# Power.net
KiCad netlist of a schematic drawn in Altium Designer
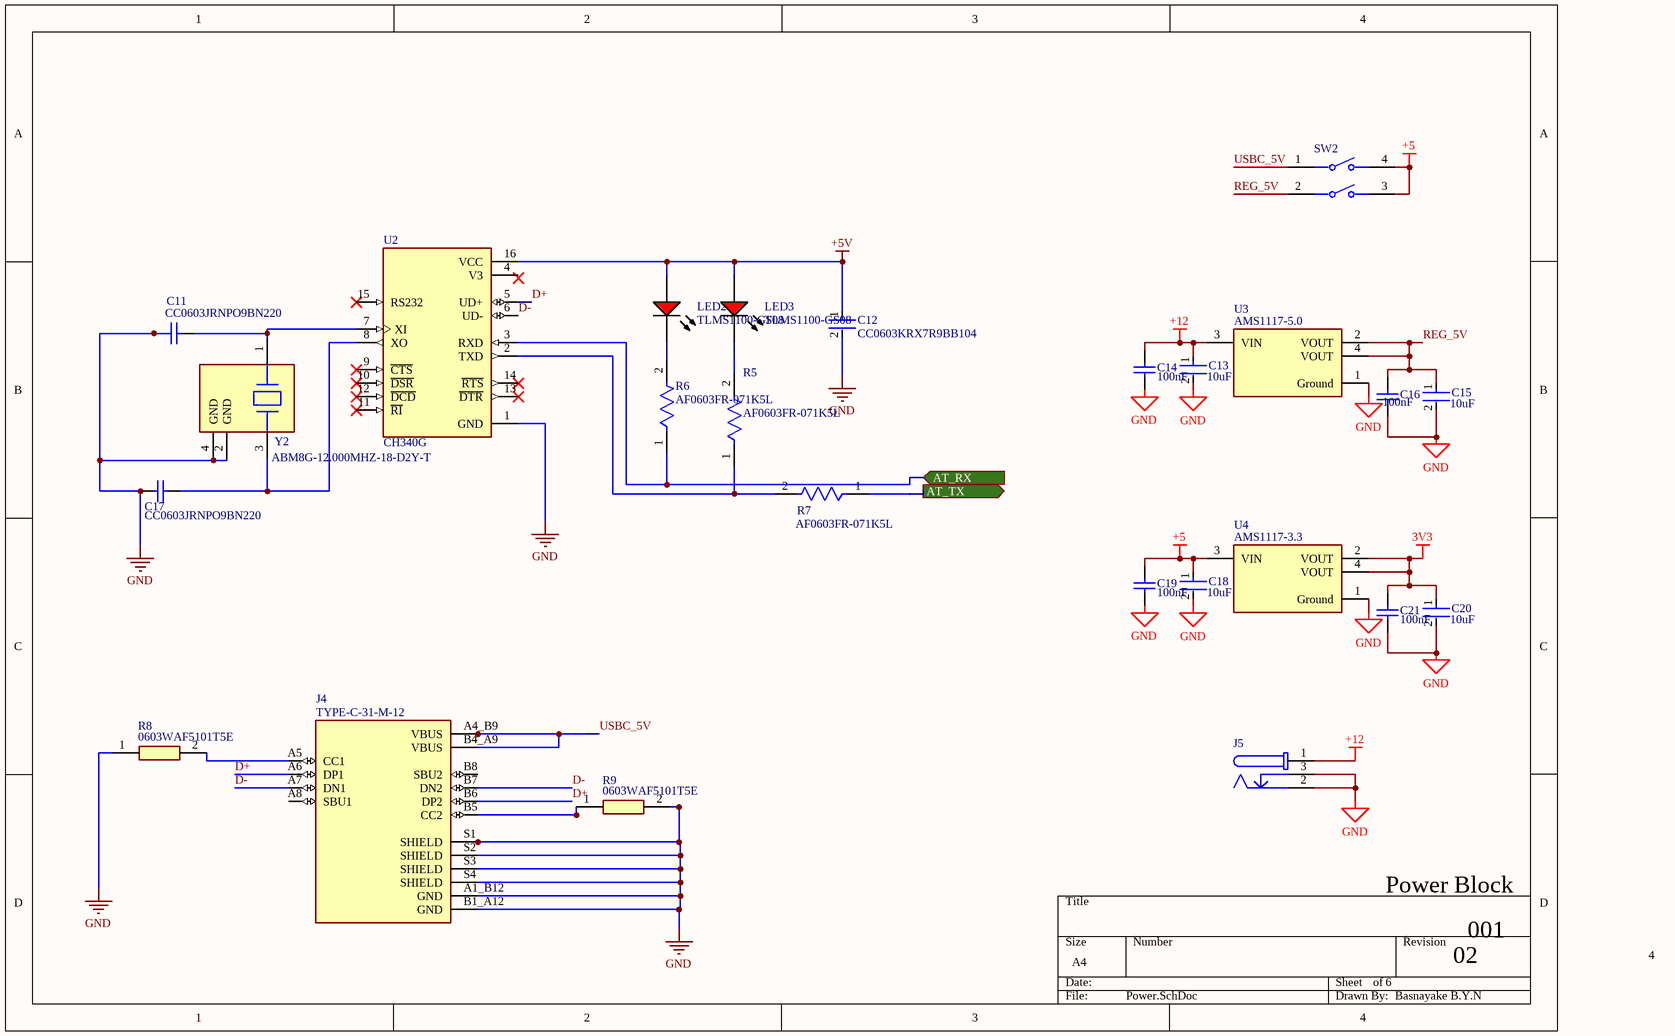
[diagram p0: Power.SchDoc]

(export (version "E")
  (design (tool "Eeschema 10.0.6"))
  (components
    (comp (ref "C11")
      (value "CC0603JRNPO9BN220")
      (footprint "CAPC1608X90X40LL10T20")
      (description "Chip Capacitor, 22 pF, +/- 5%, 50 V, -55 to 125 degC, 0603 (1608 Metric), RoHS, Tape and Reel")
      (libsource (lib "Altium Content Vault") (part "CAP-NP-2"))
    )
    (comp (ref "C12")
      (value "CC0603KRX7R9BB104")
      (footprint "FP-CC0603-DA-MFG")
      (description "CAP CER 0.1UF 50V X7R 0603")
      (fields (field (name "MANUFACTURER") "YAGEO") (field (name "VOLTAGE") "50 V"))
      (libsource (lib "Altium Content Vault") (part "11868f565c42a9108669ba33697ecf6"))
    )
    (comp (ref "C13")
      (value "1206YD106KAT2A")
      (footprint "FP-1206-L_3_2_0_2-W_1_6_0-IPC_B")
      (description "General Purpose Ceramic Capacitor, 1206, 10uF, 10%, X5R, 15%, 16V")
      (fields
        (field (name "TOLERANCE") "10%")
        (field (name "CAPACITANCE") "10uF")
        (field (name "VOLTAGE") "16V")
      )
      (libsource (lib "Altium Content Vault") (part "02cd4be3c70576c341d710602a673aa"))
    )
    (comp (ref "C14")
      (value "100nF")
      (footprint "CAPC2013X140X50LL20T25")
      (fields
        (field (name "MANUFACTURER") "AVX Interconnect / Elco")
        (field (name "PART NUMBER") "08055F104KAT2A")
      )
      (libsource (lib "Altium Content Vault") (part "CAP"))
    )
    (comp (ref "C15")
      (value "1206YD106KAT2A")
      (footprint "FP-1206-L_3_2_0_2-W_1_6_0-IPC_B")
      (description "General Purpose Ceramic Capacitor, 1206, 10uF, 10%, X5R, 15%, 16V")
      (fields
        (field (name "TOLERANCE") "10%")
        (field (name "CAPACITANCE") "10uF")
        (field (name "VOLTAGE") "16V")
      )
      (libsource (lib "Altium Content Vault") (part "02cd4be3c70576c341d710602a673aa"))
    )
    (comp (ref "C16")
      (value "100nF")
      (footprint "CAPC2013X140X50LL20T25")
      (fields
        (field (name "MANUFACTURER") "AVX Interconnect / Elco")
        (field (name "PART NUMBER") "08055F104KAT2A")
      )
      (libsource (lib "Altium Content Vault") (part "CAP"))
    )
    (comp (ref "C17")
      (value "CC0603JRNPO9BN220")
      (footprint "CAPC1608X90X40LL10T20")
      (description "Chip Capacitor, 22 pF, +/- 5%, 50 V, -55 to 125 degC, 0603 (1608 Metric), RoHS, Tape and Reel")
      (libsource (lib "Altium Content Vault") (part "CAP-NP-2"))
    )
    (comp (ref "C18")
      (value "1206YD106KAT2A")
      (footprint "FP-1206-L_3_2_0_2-W_1_6_0-IPC_B")
      (description "General Purpose Ceramic Capacitor, 1206, 10uF, 10%, X5R, 15%, 16V")
      (fields
        (field (name "TOLERANCE") "10%")
        (field (name "CAPACITANCE") "10uF")
        (field (name "VOLTAGE") "16V")
      )
      (libsource (lib "Altium Content Vault") (part "02cd4be3c70576c341d710602a673aa"))
    )
    (comp (ref "C19")
      (value "100nF")
      (footprint "CAPC2013X140X50LL20T25")
      (fields
        (field (name "MANUFACTURER") "AVX Interconnect / Elco")
        (field (name "PART NUMBER") "08055F104KAT2A")
      )
      (libsource (lib "Altium Content Vault") (part "CAP"))
    )
    (comp (ref "C20")
      (value "1206YD106KAT2A")
      (footprint "FP-1206-L_3_2_0_2-W_1_6_0-IPC_B")
      (description "General Purpose Ceramic Capacitor, 1206, 10uF, 10%, X5R, 15%, 16V")
      (fields
        (field (name "TOLERANCE") "10%")
        (field (name "CAPACITANCE") "10uF")
        (field (name "VOLTAGE") "16V")
      )
      (libsource (lib "Altium Content Vault") (part "02cd4be3c70576c341d710602a673aa"))
    )
    (comp (ref "C21")
      (value "100nF")
      (footprint "CAPC2013X140X50LL20T25")
      (fields
        (field (name "MANUFACTURER") "AVX Interconnect / Elco")
        (field (name "PART NUMBER") "08055F104KAT2A")
      )
      (libsource (lib "Altium Content Vault") (part "CAP"))
    )
    (comp (ref "J4")
      (value "TYPE-C-31-M-12")
      (footprint "HRO_TYPE-C-31-M-12")
      (description "USB Connectors 24 Receptacle 1 8.94*7.3mm RoHS")
      (fields (field (name "MF") "HRO Electronics Co., Ltd."))
      (libsource (lib "EarendelPro_Track") (part "TYPE-C-31-M-12"))
    )
    (comp (ref "J5")
      (value "694106301002")
      (footprint "694106301002")
      (libsource (lib "Altium Content Vault") (part "DC Power Jack"))
    )
    (comp (ref "LED2")
      (value "TLMS1100-GS08")
      (footprint "VISH-TLMX1100_V")
      (description "LED, RED, 2.1 V, -40 to 100 degC, 2-Pin SMD (0603), RoHS, Tape and Reel")
      (fields (field (name "TOLERANCE") "5%"))
      (libsource (lib "Altium Content Vault") (part "LED-RED-AK-2"))
    )
    (comp (ref "LED3")
      (value "TLMS1100-GS08")
      (footprint "VISH-TLMX1100_V")
      (description "LED, RED, 2.1 V, -40 to 100 degC, 2-Pin SMD (0603), RoHS, Tape and Reel")
      (fields (field (name "TOLERANCE") "5%"))
      (libsource (lib "Altium Content Vault") (part "LED-RED-AK-2"))
    )
    (comp (ref "R5")
      (value "AF0603FR-071K5L")
      (footprint "FP-AF0603-IPC_B")
      (description "Anti-Sulfurated Chip Resistors Automotive Grade 1.5kΩ 1% 100ppm/°C 0603")
      (fields (field (name "TOLERANCE") "1%"))
      (libsource (lib "Altium Content Vault") (part "1029c3af85768c4190bb7ad29bc67b5"))
    )
    (comp (ref "R6")
      (value "AF0603FR-071K5L")
      (footprint "FP-AF0603-IPC_B")
      (description "Anti-Sulfurated Chip Resistors Automotive Grade 1.5kΩ 1% 100ppm/°C 0603")
      (fields (field (name "TOLERANCE") "1%"))
      (libsource (lib "Altium Content Vault") (part "1029c3af85768c4190bb7ad29bc67b5"))
    )
    (comp (ref "R7")
      (value "AF0603FR-071K5L")
      (footprint "FP-AF0603-IPC_B")
      (description "Anti-Sulfurated Chip Resistors Automotive Grade 1.5kΩ 1% 100ppm/°C 0603")
      (fields (field (name "TOLERANCE") "1%"))
      (libsource (lib "Altium Content Vault") (part "1029c3af85768c4190bb7ad29bc67b5"))
    )
    (comp (ref "R8")
      (value "0603WAF5101T5E")
      (footprint "SamacSys:RESC1608X55N")
      (description "Resistor")
      (libsource (lib "*") (part "0603WAF5101T5E"))
    )
    (comp (ref "R9")
      (value "0603WAF5101T5E")
      (footprint "SamacSys:RESC1608X55N")
      (description "Resistor")
      (libsource (lib "*") (part "0603WAF5101T5E"))
    )
    (comp (ref "SW2")
      (value "A6T-2104")
      (footprint "FP-A6T-2104-MFG")
      (description "SWITCH SLIDE DIP SPST 25MA 24V")
      (libsource (lib "Altium Content Vault") (part "2136f0c9a6aaee9f8cd998ea1811686"))
    )
    (comp (ref "U2")
      (value "CH340G")
      (footprint "SOIC127P600X180-16N")
      (description "USB Interface Integrated Circuit")
      (fields (field (name "MF") "WCH") (field (name "MP") "Ch340G"))
      (libsource (lib "EarendelPro_Track") (part "CH340G"))
    )
    (comp (ref "U3")
      (value "AMS1117-5.0")
      (footprint "FP-AMS1117-IPC_C")
      (description "LDO Voltage Regulators 1A, 3.3V")
      (fields
        (field (name "MANUFACTURER PART NUMBER") "AMS1117-3.3")
        (field (name "OCTOPART") "https://octopart.com/ams1117-3.3-advanced+monolithic+systems-25899300")
      )
      (libsource (lib "Altium Content Vault") (part "8bdbb5f8e77002000e30dd2845d0354"))
    )
    (comp (ref "U4")
      (value "AMS1117-3.3")
      (footprint "FP-AMS1117-IPC_C")
      (description "LDO Voltage Regulators 1A, 3.3V")
      (fields
        (field (name "OCTOPART") "https://octopart.com/ams1117-3.3-advanced+monolithic+systems-25899300")
        (field (name "MANUFACTURER") "Advanced Monolithic Systems")
      )
      (libsource (lib "Altium Content Vault") (part "8bdbb5f8e77002000e30dd2845d0354"))
    )
    (comp (ref "Y2")
      (value "ABM8G-12.000MHZ-18-D2Y-T")
      (footprint "FP-ABM8G-MFG")
      (description "Crystal 12MHz ±20ppm (Tol) ±30ppm (Stability) 18pF FUND 120Ω 4-Pin SMD T/R")
      (fields (field (name "TOLERANCE") "20ppm"))
      (libsource (lib "Altium Content Vault") (part "48e526d86b7f2615d98721063c72f49"))
    )
  )
  (nets
    (net (code "1") (name "+5") (class "Default")
      (node (ref "C18") (pin "1") (pinfunction "1_1") (pintype "passive"))
      (node (ref "C19") (pin "2") (pinfunction "2_2") (pintype "passive"))
      (node (ref "SW2") (pin "3") (pinfunction "3_3") (pintype "passive"))
      (node (ref "SW2") (pin "4") (pinfunction "4_4") (pintype "passive"))
      (node (ref "U4") (pin "3") (pinfunction "VIN_3") (pintype "power_in"))
    )
    (net (code "2") (name "+5V") (class "Default")
      (node (ref "C12") (pin "1") (pinfunction "1_1") (pintype "passive"))
      (node (ref "LED2") (pin "1") (pinfunction "A_1") (pintype "passive"))
      (node (ref "LED3") (pin "1") (pinfunction "A_1") (pintype "passive"))
      (node (ref "U2") (pin "16") (pinfunction "VCC_16") (pintype "power_in"))
    )
    (net (code "3") (name "+12") (class "Default")
      (node (ref "C13") (pin "1") (pinfunction "1_1") (pintype "passive"))
      (node (ref "C14") (pin "2") (pinfunction "2_2") (pintype "passive"))
      (node (ref "J5") (pin "1") (pinfunction "1_1") (pintype "passive"))
      (node (ref "U3") (pin "3") (pinfunction "VIN_3") (pintype "power_in"))
    )
    (net (code "4") (name "/AT_RX") (class "Default")
      (node (ref "R6") (pin "1") (pinfunction "1_1") (pintype "passive"))
      (node (ref "U2") (pin "3") (pinfunction "RXD_3") (pintype "input"))
    )
    (net (code "5") (name "/AT_TX") (class "Default")
      (node (ref "R7") (pin "1") (pinfunction "1_1") (pintype "passive"))
    )
    (net (code "6") (name "/D+") (class "Default")
      (node (ref "J4") (pin "A6") (pinfunction "DP1_A6") (pintype "bidirectional"))
      (node (ref "J4") (pin "B6") (pinfunction "DP2_B6") (pintype "bidirectional"))
      (node (ref "U2") (pin "5") (pinfunction "UD+_5") (pintype "bidirectional"))
    )
    (net (code "7") (name "/D-") (class "Default")
      (node (ref "J4") (pin "A7") (pinfunction "DN1_A7") (pintype "bidirectional"))
      (node (ref "J4") (pin "B7") (pinfunction "DN2_B7") (pintype "bidirectional"))
      (node (ref "U2") (pin "6") (pinfunction "UD-_6") (pintype "bidirectional"))
    )
    (net (code "8") (name "/REG_5V") (class "Default")
      (node (ref "C15") (pin "1") (pinfunction "1_1") (pintype "passive"))
      (node (ref "C16") (pin "2") (pinfunction "2_2") (pintype "passive"))
      (node (ref "SW2") (pin "2") (pinfunction "2_2") (pintype "passive"))
      (node (ref "U3") (pin "2") (pinfunction "VOUT_2") (pintype "passive"))
      (node (ref "U3") (pin "4") (pinfunction "VOUT_4") (pintype "passive"))
    )
    (net (code "9") (name "/USBC_5V") (class "Default")
      (node (ref "J4") (pin "A4_B9") (pinfunction "VBUS_A4_B9") (pintype "power_in"))
      (node (ref "J4") (pin "B4_A9") (pinfunction "VBUS_B4_A9") (pintype "power_in"))
      (node (ref "SW2") (pin "1") (pinfunction "1_1") (pintype "passive"))
    )
    (net (code "10") (name "3V3") (class "Default")
      (node (ref "C20") (pin "1") (pinfunction "1_1") (pintype "passive"))
      (node (ref "C21") (pin "2") (pinfunction "2_2") (pintype "passive"))
      (node (ref "U4") (pin "2") (pinfunction "VOUT_2") (pintype "passive"))
      (node (ref "U4") (pin "4") (pinfunction "VOUT_4") (pintype "passive"))
    )
    (net (code "11") (name "GND") (class "Default")
      (node (ref "C11") (pin "1") (pinfunction "1_1") (pintype "passive"))
      (node (ref "C12") (pin "2") (pinfunction "2_2") (pintype "passive"))
      (node (ref "C13") (pin "2") (pinfunction "2_2") (pintype "passive"))
      (node (ref "C14") (pin "1") (pinfunction "1_1") (pintype "passive"))
      (node (ref "C15") (pin "2") (pinfunction "2_2") (pintype "passive"))
      (node (ref "C16") (pin "1") (pinfunction "1_1") (pintype "passive"))
      (node (ref "C17") (pin "1") (pinfunction "1_1") (pintype "passive"))
      (node (ref "C18") (pin "2") (pinfunction "2_2") (pintype "passive"))
      (node (ref "C19") (pin "1") (pinfunction "1_1") (pintype "passive"))
      (node (ref "C20") (pin "2") (pinfunction "2_2") (pintype "passive"))
      (node (ref "C21") (pin "1") (pinfunction "1_1") (pintype "passive"))
      (node (ref "J4") (pin "A1_B12") (pinfunction "GND_A1_B12") (pintype "power_in"))
      (node (ref "J4") (pin "B1_A12") (pinfunction "GND_B1_A12") (pintype "power_in"))
      (node (ref "J4") (pin "S1") (pinfunction "SHIELD_S1") (pintype "passive"))
      (node (ref "J4") (pin "S2") (pinfunction "SHIELD_S2") (pintype "passive"))
      (node (ref "J4") (pin "S3") (pinfunction "SHIELD_S3") (pintype "passive"))
      (node (ref "J4") (pin "S4") (pinfunction "SHIELD_S4") (pintype "passive"))
      (node (ref "J5") (pin "2") (pinfunction "2_2") (pintype "passive"))
      (node (ref "J5") (pin "3") (pinfunction "3_3") (pintype "passive"))
      (node (ref "R8") (pin "1") (pinfunction "1_1") (pintype "passive"))
      (node (ref "R9") (pin "2") (pinfunction "2_2") (pintype "passive"))
      (node (ref "U2") (pin "1") (pinfunction "GND_1") (pintype "power_in"))
      (node (ref "U3") (pin "1") (pinfunction "Ground_1") (pintype "power_in"))
      (node (ref "U4") (pin "1") (pinfunction "Ground_1") (pintype "power_in"))
      (node (ref "Y2") (pin "2") (pinfunction "GND_2") (pintype "power_in"))
      (node (ref "Y2") (pin "4") (pinfunction "GND_4") (pintype "power_in"))
    )
    (net (code "12") (name "Net-(J4-CC1)") (class "Default")
      (node (ref "J4") (pin "A5") (pinfunction "CC1_A5") (pintype "bidirectional"))
      (node (ref "R8") (pin "2") (pinfunction "2_2") (pintype "passive"))
    )
    (net (code "13") (name "Net-(J4-CC2)") (class "Default")
      (node (ref "J4") (pin "B5") (pinfunction "CC2_B5") (pintype "bidirectional"))
      (node (ref "R9") (pin "1") (pinfunction "1_1") (pintype "passive"))
    )
    (net (code "14") (name "Net-(LED2-K)") (class "Default")
      (node (ref "LED2") (pin "2") (pinfunction "K_2") (pintype "passive"))
      (node (ref "R6") (pin "2") (pinfunction "2_2") (pintype "passive"))
    )
    (net (code "15") (name "Net-(LED3-K)") (class "Default")
      (node (ref "LED3") (pin "2") (pinfunction "K_2") (pintype "passive"))
      (node (ref "R5") (pin "2") (pinfunction "2_2") (pintype "passive"))
    )
    (net (code "16") (name "Net-(U2-TXD)") (class "Default")
      (node (ref "R5") (pin "1") (pinfunction "1_1") (pintype "passive"))
      (node (ref "R7") (pin "2") (pinfunction "2_2") (pintype "passive"))
      (node (ref "U2") (pin "2") (pinfunction "TXD_2") (pintype "output"))
    )
    (net (code "17") (name "Net-(U2-XI)") (class "Default")
      (node (ref "C11") (pin "2") (pinfunction "2_2") (pintype "passive"))
      (node (ref "U2") (pin "7") (pinfunction "XI_7") (pintype "input"))
      (node (ref "Y2") (pin "1") (pinfunction "1_1") (pintype "passive"))
    )
    (net (code "18") (name "Net-(U2-XO)") (class "Default")
      (node (ref "C17") (pin "2") (pinfunction "2_2") (pintype "passive"))
      (node (ref "U2") (pin "8") (pinfunction "XO_8") (pintype "output"))
      (node (ref "Y2") (pin "3") (pinfunction "3_3") (pintype "passive"))
    )
    (net (code "19") (name "unconnected-(J4-SBU1-PadA8)") (class "Default")
      (node (ref "J4") (pin "A8") (pinfunction "SBU1_A8") (pintype "bidirectional"))
    )
    (net (code "20") (name "unconnected-(J4-SBU2-PadB8)") (class "Default")
      (node (ref "J4") (pin "B8") (pinfunction "SBU2_B8") (pintype "bidirectional"))
    )
    (net (code "21") (name "unconnected-(U2-RS232-Pad15)") (class "Default")
      (node (ref "U2") (pin "15") (pinfunction "RS232_15") (pintype "input+no_connect"))
    )
    (net (code "22") (name "unconnected-(U2-V3-Pad4)") (class "Default")
      (node (ref "U2") (pin "4") (pinfunction "V3_4") (pintype "power_in"))
    )
    (net (code "23") (name "unconnected-(U2-~{CTS}-Pad9)") (class "Default")
      (node (ref "U2") (pin "9") (pinfunction "~{CTS}_9") (pintype "input+no_connect"))
    )
    (net (code "24") (name "unconnected-(U2-~{DCD}-Pad12)") (class "Default")
      (node (ref "U2") (pin "12") (pinfunction "~{DCD}_12") (pintype "input+no_connect"))
    )
    (net (code "25") (name "unconnected-(U2-~{DSR}-Pad10)") (class "Default")
      (node (ref "U2") (pin "10") (pinfunction "~{DSR}_10") (pintype "input+no_connect"))
    )
    (net (code "26") (name "unconnected-(U2-~{DTR}-Pad13)") (class "Default")
      (node (ref "U2") (pin "13") (pinfunction "~{DTR}_13") (pintype "output+no_connect"))
    )
    (net (code "27") (name "unconnected-(U2-~{RI}-Pad11)") (class "Default")
      (node (ref "U2") (pin "11") (pinfunction "~{RI}_11") (pintype "input+no_connect"))
    )
    (net (code "28") (name "unconnected-(U2-~{RTS}-Pad14)") (class "Default")
      (node (ref "U2") (pin "14") (pinfunction "~{RTS}_14") (pintype "output+no_connect"))
    )
  )
)
